# SML-230109PCB1__NFC.net
KiCad netlist of a schematic drawn in Altium Designer
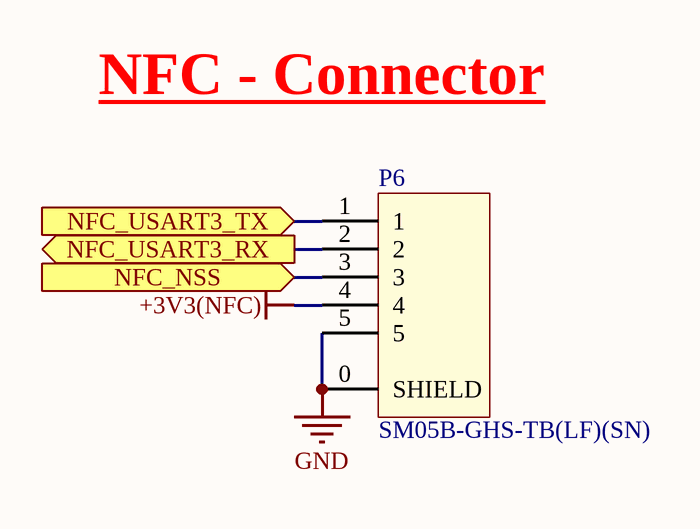
[diagram p0: SML-230109PCB1__NFC.SchDoc]

(export (version "E")
  (design (tool "Eeschema 10.0.6"))
  (components
    (comp (ref "P6")
      (value ".")
      (footprint "CONN-SMD__JST(5PIN)__SM05B-GHS-TB(LF)(SN)")
      (description "CONN SMD, JST, side entry, 1x5pin, with lock, 1A, 50V")
      (fields (field (name "[01] - MPN CODE") "SM05B-GHS-TB(LF)(SN)"))
      (libsource (lib "DEB_LIB_SCH_22-03") (part "SM05B-GHS-TB(LF)(SN)"))
    )
  )
  (nets
    (net (code "1") (name "+3V3(NFC)") (class "Default")
      (node (ref "P6") (pin "4") (pinfunction "4_4") (pintype "passive"))
    )
    (net (code "2") (name "/NFC_NSS") (class "Default")
      (node (ref "P6") (pin "3") (pinfunction "3_3") (pintype "passive"))
    )
    (net (code "3") (name "/NFC_USART3_RX") (class "Default")
      (node (ref "P6") (pin "2") (pinfunction "2_2") (pintype "passive"))
    )
    (net (code "4") (name "/NFC_USART3_TX") (class "Default")
      (node (ref "P6") (pin "1") (pinfunction "1_1") (pintype "passive"))
    )
    (net (code "5") (name "GND") (class "Default")
      (node (ref "P6") (pin "0") (pinfunction "SHIELD_0") (pintype "passive"))
      (node (ref "P6") (pin "5") (pinfunction "5_5") (pintype "passive"))
    )
  )
)
